# LED_external.net
KiCad netlist of a schematic drawn in Altium Designer
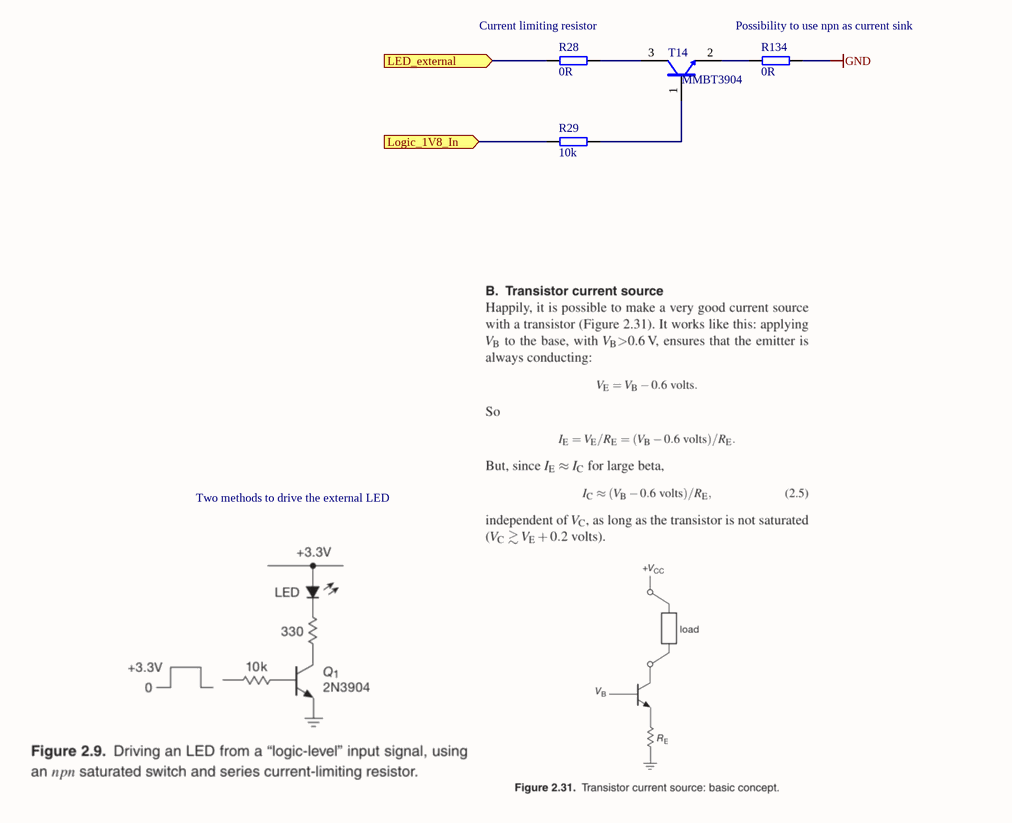
[diagram p0: LED_external.SchDoc]

(export (version "E")
  (design (tool "Eeschema 10.0.6"))
  (components
    (comp (ref "R28")
      (value "0R")
      (footprint "R_0603_TE")
      (description "Generic resistor")
      (fields
        (field (name "TOLERANCE") "1 %")
        (field (name "MANUFACTURER PART NUMBER") "UZgen_R_0603_0R")
        (field (name "CREATED FROM") "UZgenTool")
      )
      (libsource (lib "user") (part "RES"))
    )
    (comp (ref "R29")
      (value "10k")
      (footprint "R_0603_TE")
      (description "Generic resistor")
      (fields
        (field (name "TOLERANCE") "1 %")
        (field (name "MANUFACTURER PART NUMBER") "UZgen_R_0603_10k")
        (field (name "CREATED FROM") "AGeiger")
      )
      (libsource (lib "user") (part "RES"))
    )
    (comp (ref "R134")
      (value "0R")
      (footprint "R_0603_TE")
      (description "Generic resistor")
      (fields
        (field (name "TOLERANCE") "1 %")
        (field (name "MANUFACTURER PART NUMBER") "UZgen_R_0603_0R")
        (field (name "CREATED FROM") "UZgenTool")
      )
      (libsource (lib "user") (part "RES"))
    )
    (comp (ref "T14")
      (value "MMBT3904")
      (footprint "SOT95P280X145-3N")
      (libsource (lib "TE") (part "NPN-SOT23"))
    )
  )
  (nets
    (net (code "1") (name "/LED_external") (class "Default")
      (node (ref "R28") (pin "2") (pinfunction "2_2") (pintype "passive"))
    )
    (net (code "2") (name "/Logic_1V8_In") (class "Default")
      (node (ref "R29") (pin "1") (pinfunction "1_1") (pintype "passive"))
    )
    (net (code "3") (name "GND") (class "Default")
      (node (ref "R134") (pin "1") (pinfunction "1_1") (pintype "passive"))
    )
    (net (code "4") (name "Net-(T14-BASIS)") (class "Default")
      (node (ref "R29") (pin "2") (pinfunction "2_2") (pintype "passive"))
      (node (ref "T14") (pin "1") (pinfunction "BASIS_1") (pintype "passive"))
    )
    (net (code "5") (name "Net-(T14-COLLECTOR)") (class "Default")
      (node (ref "R28") (pin "1") (pinfunction "1_1") (pintype "passive"))
      (node (ref "T14") (pin "3") (pinfunction "COLLECTOR_3") (pintype "passive"))
    )
    (net (code "6") (name "Net-(T14-EMITTER)") (class "Default")
      (node (ref "R134") (pin "2") (pinfunction "2_2") (pintype "passive"))
      (node (ref "T14") (pin "2") (pinfunction "EMITTER_2") (pintype "passive"))
    )
  )
)
